# exoShield.net
KiCad netlist of a schematic drawn in EAGLE
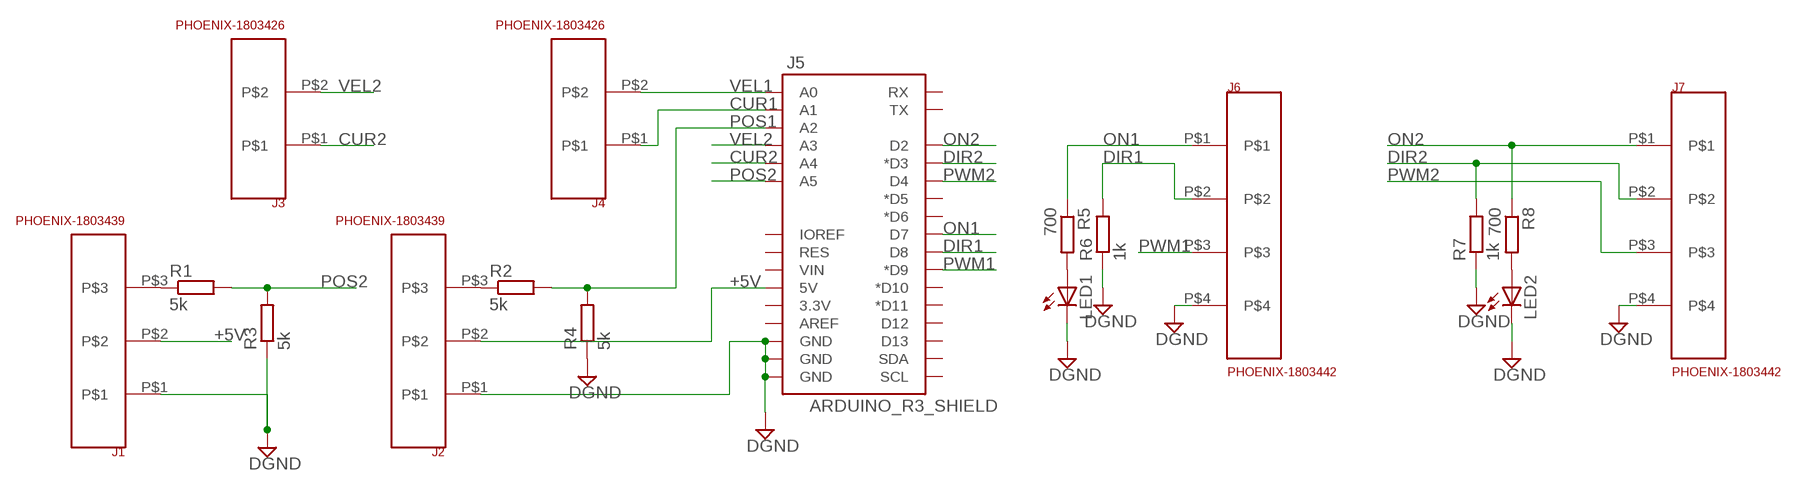
[diagram p0: schematic, sheet 1]

(export (version "E")
  (design (tool "Eeschema 10.0.6"))
  (components
    (comp (ref "J1")
      (value "PHOENIX-1803439")
      (footprint "eagle-import:PHOENIX-1803439")
      (libsource (lib "eagle-import") (part "PHOENIX-1803439"))
    )
    (comp (ref "J2")
      (value "PHOENIX-1803439")
      (footprint "eagle-import:PHOENIX-1803439")
      (libsource (lib "eagle-import") (part "PHOENIX-1803439"))
    )
    (comp (ref "J3")
      (value "PHOENIX-1803426")
      (footprint "eagle-import:PHOENIX-1803426")
      (libsource (lib "eagle-import") (part "PHOENIX-1803426"))
    )
    (comp (ref "J4")
      (value "PHOENIX-1803426")
      (footprint "eagle-import:PHOENIX-1803426")
      (libsource (lib "eagle-import") (part "PHOENIX-1803426"))
    )
    (comp (ref "J5")
      (value "ARDUINO_R3_SHIELD")
      (footprint "eagle-import:UNO_R3_SHIELD")
      (libsource (lib "eagle-import") (part "ARDUINO_R3_SHIELD"))
    )
    (comp (ref "J6")
      (value "PHOENIX-1803442")
      (footprint "eagle-import:PHOENIX-1803442")
      (libsource (lib "eagle-import") (part "PHOENIX-1803442"))
    )
    (comp (ref "J7")
      (value "PHOENIX-1803442")
      (footprint "eagle-import:PHOENIX-1803442")
      (libsource (lib "eagle-import") (part "PHOENIX-1803442"))
    )
    (comp (ref "LED1")
      (value "LED3MM")
      (footprint "eagle-import:LED3MM")
      (libsource (lib "eagle-import") (part "LED3MM"))
    )
    (comp (ref "LED2")
      (value "LED3MM")
      (footprint "eagle-import:LED3MM")
      (libsource (lib "eagle-import") (part "LED3MM"))
    )
    (comp (ref "R1")
      (value "5k")
      (footprint "eagle-import:0207_10")
      (libsource (lib "eagle-import") (part "R-EU_0207/10"))
    )
    (comp (ref "R2")
      (value "5k")
      (footprint "eagle-import:0207_10")
      (libsource (lib "eagle-import") (part "R-EU_0207/10"))
    )
    (comp (ref "R3")
      (value "5k")
      (footprint "eagle-import:0207_10")
      (libsource (lib "eagle-import") (part "R-EU_0207/10"))
    )
    (comp (ref "R4")
      (value "5k")
      (footprint "eagle-import:0207_10")
      (libsource (lib "eagle-import") (part "R-EU_0207/10"))
    )
    (comp (ref "R5")
      (value "700")
      (footprint "eagle-import:0207_10")
      (libsource (lib "eagle-import") (part "R-EU_0207/10"))
    )
    (comp (ref "R6")
      (value "1k")
      (footprint "eagle-import:0207_10")
      (libsource (lib "eagle-import") (part "R-EU_0207/10"))
    )
    (comp (ref "R7")
      (value "1k")
      (footprint "eagle-import:0207_10")
      (libsource (lib "eagle-import") (part "R-EU_0207/10"))
    )
    (comp (ref "R8")
      (value "700")
      (footprint "eagle-import:0207_10")
      (libsource (lib "eagle-import") (part "R-EU_0207/10"))
    )
  )
  (nets
    (net (code "1") (name "/+5V") (class "Default")
      (node (ref "J1") (pin "P$2") (pinfunction "P$2_P$2") (pintype "bidirectional"))
      (node (ref "J2") (pin "P$2") (pinfunction "P$2_P$2") (pintype "bidirectional"))
      (node (ref "J5") (pin "5V") (pinfunction "5V_5V") (pintype "bidirectional"))
    )
    (net (code "2") (name "/CUR1") (class "Default")
      (node (ref "J4") (pin "P$1") (pinfunction "P$1_P$1") (pintype "bidirectional"))
      (node (ref "J5") (pin "A1") (pinfunction "A1_A1") (pintype "bidirectional"))
    )
    (net (code "3") (name "/CUR2") (class "Default")
      (node (ref "J3") (pin "P$1") (pinfunction "P$1_P$1") (pintype "bidirectional"))
      (node (ref "J5") (pin "A4") (pinfunction "A4_A4") (pintype "bidirectional"))
    )
    (net (code "4") (name "/DIR1") (class "Default")
      (node (ref "J5") (pin "D8") (pinfunction "D8_D8") (pintype "bidirectional"))
      (node (ref "J6") (pin "P$2") (pinfunction "P$2_P$2") (pintype "bidirectional"))
      (node (ref "R6") (pin "2") (pinfunction "2_2") (pintype "passive"))
    )
    (net (code "5") (name "/DIR2") (class "Default")
      (node (ref "J5") (pin "D3") (pinfunction "*D3_D3") (pintype "bidirectional"))
      (node (ref "J7") (pin "P$2") (pinfunction "P$2_P$2") (pintype "bidirectional"))
      (node (ref "R7") (pin "2") (pinfunction "2_2") (pintype "passive"))
    )
    (net (code "6") (name "/ON1") (class "Default")
      (node (ref "J5") (pin "D7") (pinfunction "D7_D7") (pintype "bidirectional"))
      (node (ref "J6") (pin "P$1") (pinfunction "P$1_P$1") (pintype "bidirectional"))
      (node (ref "R5") (pin "1") (pinfunction "1_1") (pintype "passive"))
    )
    (net (code "7") (name "/ON2") (class "Default")
      (node (ref "J5") (pin "D2") (pinfunction "D2_D2") (pintype "bidirectional"))
      (node (ref "J7") (pin "P$1") (pinfunction "P$1_P$1") (pintype "bidirectional"))
      (node (ref "R8") (pin "1") (pinfunction "1_1") (pintype "passive"))
    )
    (net (code "8") (name "/POS1") (class "Default")
      (node (ref "J5") (pin "A2") (pinfunction "A2_A2") (pintype "bidirectional"))
      (node (ref "R2") (pin "2") (pinfunction "2_2") (pintype "passive"))
      (node (ref "R4") (pin "2") (pinfunction "2_2") (pintype "passive"))
    )
    (net (code "9") (name "/POS2") (class "Default")
      (node (ref "J5") (pin "A5") (pinfunction "A5_A5") (pintype "bidirectional"))
      (node (ref "R1") (pin "2") (pinfunction "2_2") (pintype "passive"))
      (node (ref "R3") (pin "2") (pinfunction "2_2") (pintype "passive"))
    )
    (net (code "10") (name "/PWM1") (class "Default")
      (node (ref "J5") (pin "D9") (pinfunction "*D9_D9") (pintype "bidirectional"))
      (node (ref "J6") (pin "P$3") (pinfunction "P$3_P$3") (pintype "bidirectional"))
    )
    (net (code "11") (name "/PWM2") (class "Default")
      (node (ref "J5") (pin "D4") (pinfunction "D4_D4") (pintype "bidirectional"))
      (node (ref "J7") (pin "P$3") (pinfunction "P$3_P$3") (pintype "bidirectional"))
    )
    (net (code "12") (name "/VEL1") (class "Default")
      (node (ref "J4") (pin "P$2") (pinfunction "P$2_P$2") (pintype "bidirectional"))
      (node (ref "J5") (pin "A0") (pinfunction "A0_A0") (pintype "bidirectional"))
    )
    (net (code "13") (name "/VEL2") (class "Default")
      (node (ref "J3") (pin "P$2") (pinfunction "P$2_P$2") (pintype "bidirectional"))
      (node (ref "J5") (pin "A3") (pinfunction "A3_A3") (pintype "bidirectional"))
    )
    (net (code "14") (name "DGND") (class "Default")
      (node (ref "J1") (pin "P$1") (pinfunction "P$1_P$1") (pintype "bidirectional"))
      (node (ref "J2") (pin "P$1") (pinfunction "P$1_P$1") (pintype "bidirectional"))
      (node (ref "J5") (pin "GND@0") (pinfunction "GND_GND@0") (pintype "bidirectional"))
      (node (ref "J5") (pin "GND@1") (pinfunction "GND_GND@1") (pintype "bidirectional"))
      (node (ref "J5") (pin "GND@2") (pinfunction "GND_GND@2") (pintype "bidirectional"))
      (node (ref "J6") (pin "P$4") (pinfunction "P$4_P$4") (pintype "bidirectional"))
      (node (ref "J7") (pin "P$4") (pinfunction "P$4_P$4") (pintype "bidirectional"))
      (node (ref "LED1") (pin "K") (pinfunction "C_K") (pintype "passive"))
      (node (ref "LED2") (pin "K") (pinfunction "C_K") (pintype "passive"))
      (node (ref "R3") (pin "1") (pinfunction "1_1") (pintype "passive"))
      (node (ref "R4") (pin "1") (pinfunction "1_1") (pintype "passive"))
      (node (ref "R6") (pin "1") (pinfunction "1_1") (pintype "passive"))
      (node (ref "R7") (pin "1") (pinfunction "1_1") (pintype "passive"))
    )
    (net (code "15") (name "Net-(J1-PadP$3)") (class "Default")
      (node (ref "J1") (pin "P$3") (pinfunction "P$3_P$3") (pintype "bidirectional"))
      (node (ref "R1") (pin "1") (pinfunction "1_1") (pintype "passive"))
    )
    (net (code "16") (name "Net-(J2-PadP$3)") (class "Default")
      (node (ref "J2") (pin "P$3") (pinfunction "P$3_P$3") (pintype "bidirectional"))
      (node (ref "R2") (pin "1") (pinfunction "1_1") (pintype "passive"))
    )
    (net (code "17") (name "Net-(LED1-PadA)") (class "Default")
      (node (ref "LED1") (pin "A") (pinfunction "A_A") (pintype "passive"))
      (node (ref "R5") (pin "2") (pinfunction "2_2") (pintype "passive"))
    )
    (net (code "18") (name "Net-(LED2-PadA)") (class "Default")
      (node (ref "LED2") (pin "A") (pinfunction "A_A") (pintype "passive"))
      (node (ref "R8") (pin "2") (pinfunction "2_2") (pintype "passive"))
    )
    (net (code "19") (name "unconnected-(J5-*D5-PadD5)") (class "Default")
      (node (ref "J5") (pin "D5") (pinfunction "*D5_D5") (pintype "bidirectional"))
    )
    (net (code "20") (name "unconnected-(J5-*D6-PadD6)") (class "Default")
      (node (ref "J5") (pin "D6") (pinfunction "*D6_D6") (pintype "bidirectional"))
    )
    (net (code "21") (name "unconnected-(J5-*D10-PadD10)") (class "Default")
      (node (ref "J5") (pin "D10") (pinfunction "*D10_D10") (pintype "bidirectional"))
    )
    (net (code "22") (name "unconnected-(J5-*D11-PadD11)") (class "Default")
      (node (ref "J5") (pin "D11") (pinfunction "*D11_D11") (pintype "bidirectional"))
    )
    (net (code "23") (name "unconnected-(J5-Pad3.3V)") (class "Default")
      (node (ref "J5") (pin "3.3V") (pinfunction "3.3V_3.3V") (pintype "bidirectional"))
    )
    (net (code "24") (name "unconnected-(J5-PadAREF)") (class "Default")
      (node (ref "J5") (pin "AREF") (pinfunction "AREF_AREF") (pintype "bidirectional"))
    )
    (net (code "25") (name "unconnected-(J5-PadD12)") (class "Default")
      (node (ref "J5") (pin "D12") (pinfunction "D12_D12") (pintype "bidirectional"))
    )
    (net (code "26") (name "unconnected-(J5-PadD13)") (class "Default")
      (node (ref "J5") (pin "D13") (pinfunction "D13_D13") (pintype "bidirectional"))
    )
    (net (code "27") (name "unconnected-(J5-PadIOREF)") (class "Default")
      (node (ref "J5") (pin "IOREF") (pinfunction "IOREF_IOREF") (pintype "bidirectional"))
    )
    (net (code "28") (name "unconnected-(J5-PadRES)") (class "Default")
      (node (ref "J5") (pin "RES") (pinfunction "RES_RES") (pintype "bidirectional"))
    )
    (net (code "29") (name "unconnected-(J5-PadRX)") (class "Default")
      (node (ref "J5") (pin "RX") (pinfunction "RX_RX") (pintype "bidirectional"))
    )
    (net (code "30") (name "unconnected-(J5-PadSCL)") (class "Default")
      (node (ref "J5") (pin "SCL") (pinfunction "SCL_SCL") (pintype "bidirectional"))
    )
    (net (code "31") (name "unconnected-(J5-PadSDA)") (class "Default")
      (node (ref "J5") (pin "SDA") (pinfunction "SDA_SDA") (pintype "bidirectional"))
    )
    (net (code "32") (name "unconnected-(J5-PadTX)") (class "Default")
      (node (ref "J5") (pin "TX") (pinfunction "TX_TX") (pintype "bidirectional"))
    )
    (net (code "33") (name "unconnected-(J5-PadVIN)") (class "Default")
      (node (ref "J5") (pin "VIN") (pinfunction "VIN_VIN") (pintype "bidirectional"))
    )
  )
)
